# 2312_Ethernet.net
KiCad netlist of a schematic drawn in Altium Designer
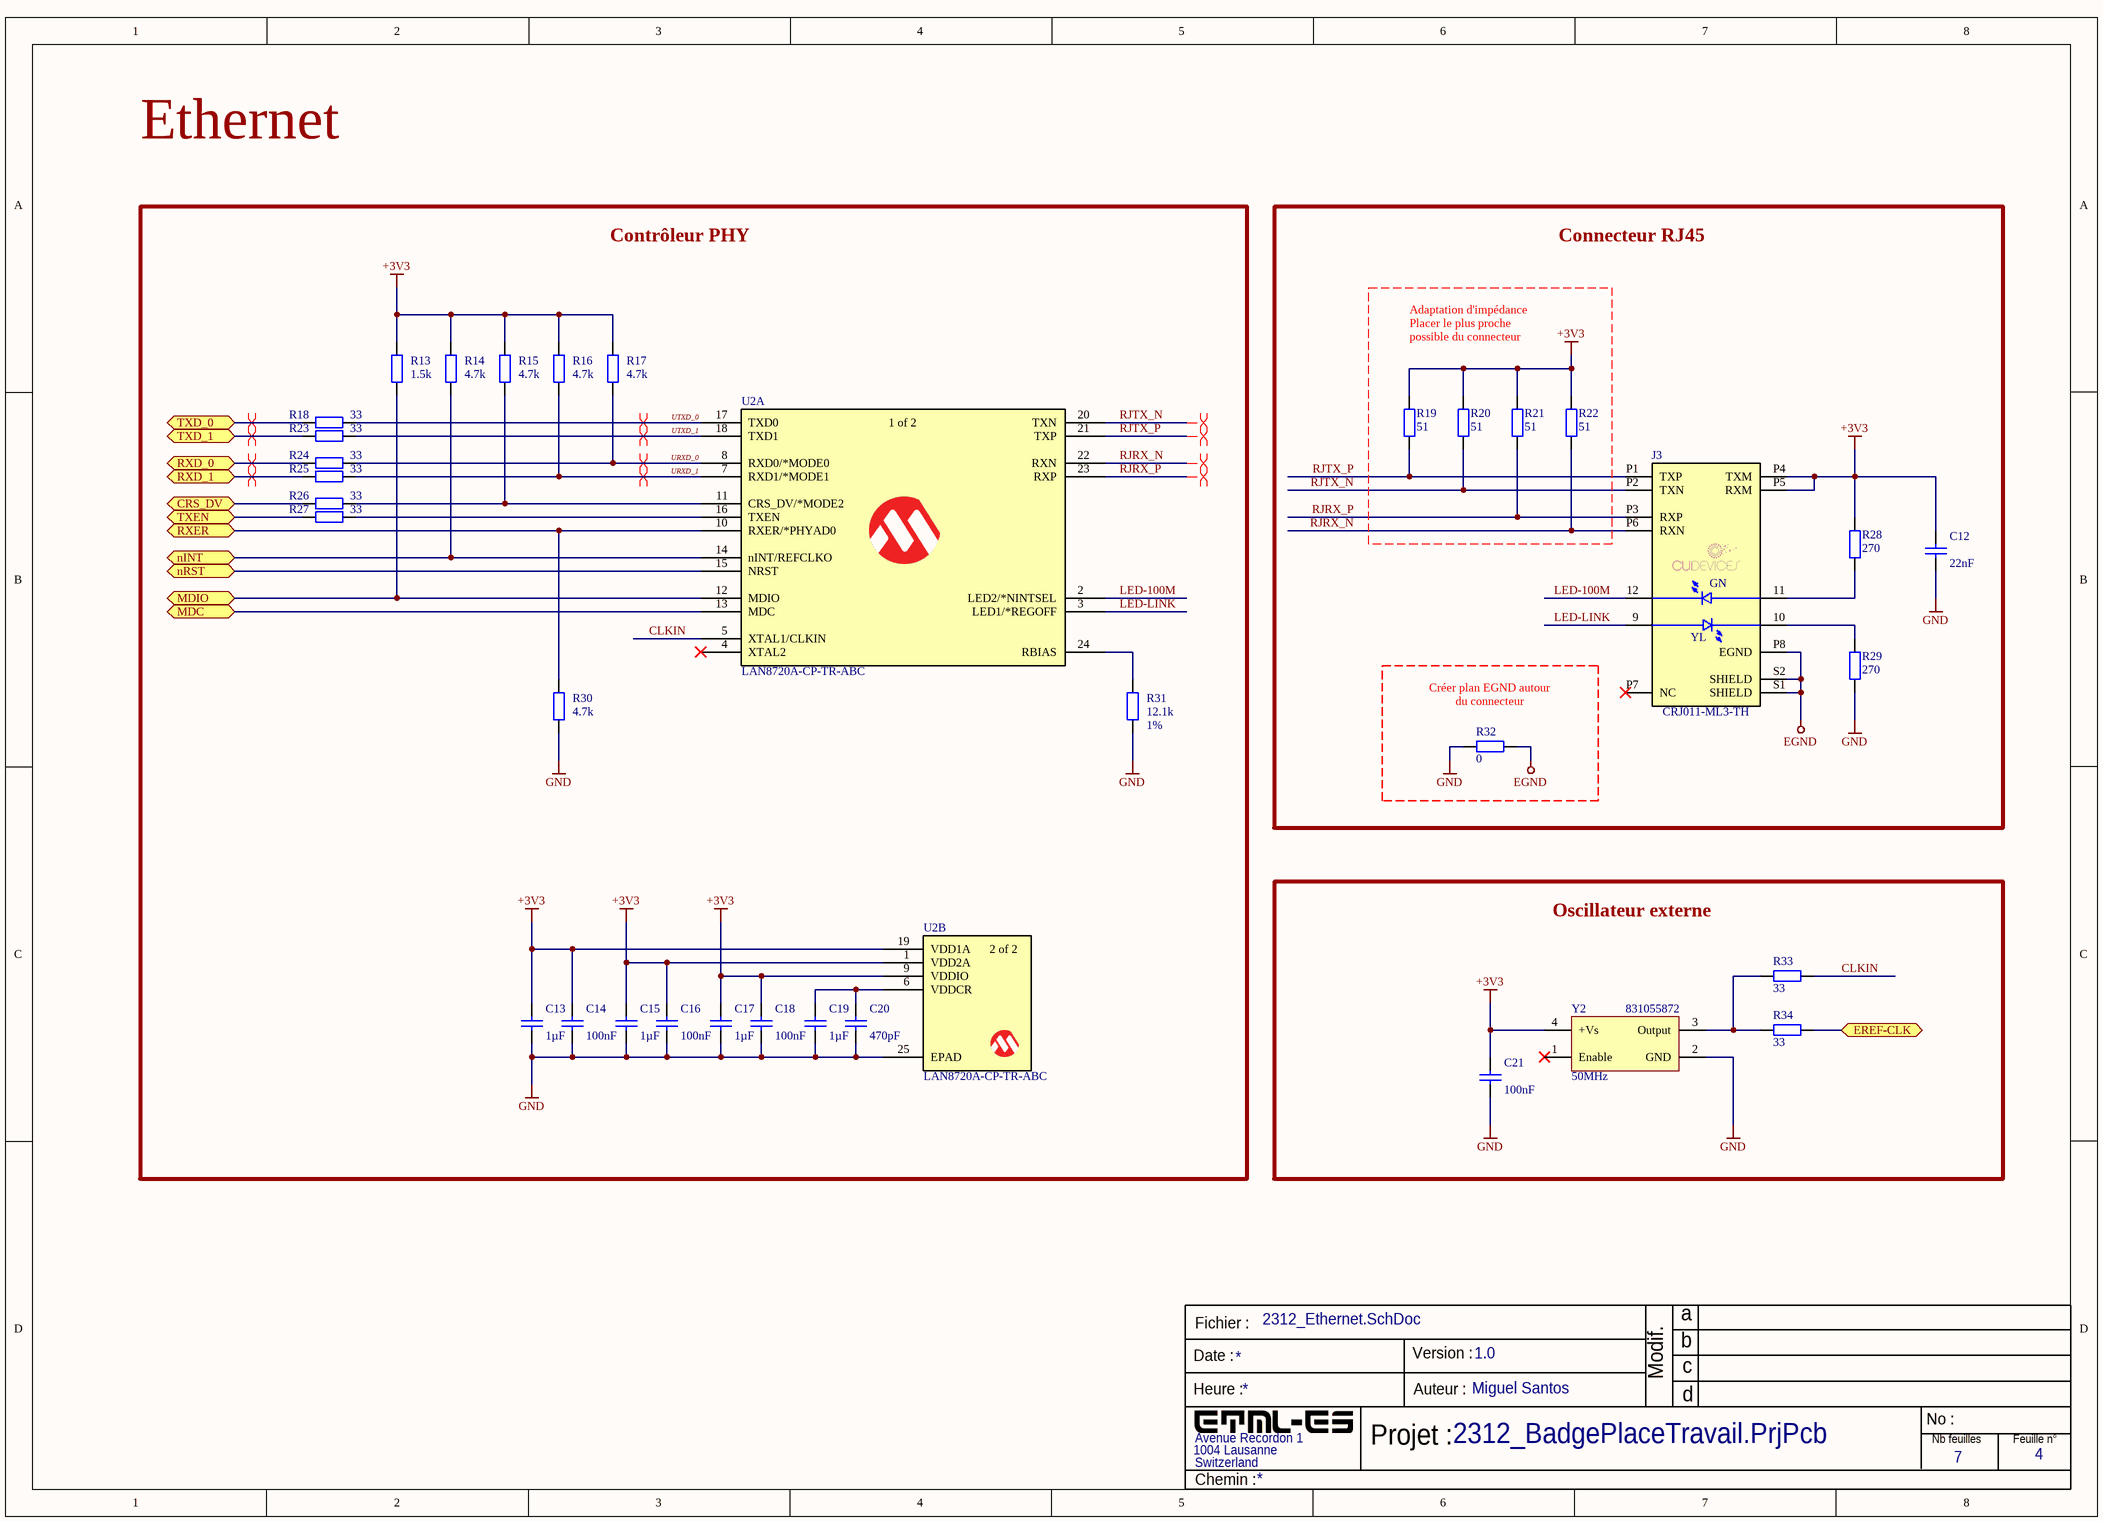
[diagram p0: 2312_Ethernet.SchDoc]

(export (version "E")
  (design (tool "Eeschema 10.0.6"))
  (components
    (comp (ref "C12")
      (value "885012207013")
      (footprint "WCAP-CSGP_0805_L2W1.25H0.8_Reflow")
      (description "WCAP-CSGP Multilayer Ceramic Chip Capacitor, General Purpose, size 0805, X7R, 22nF, 10VDC")
      (fields (field (name "MANUFACTURER") "Wurth Elektronik") (field (name "CAPACITANCE") "22nF"))
      (libsource (lib "WCAP-CSGP") (part "885012207013"))
    )
    (comp (ref "C13")
      (value "885012207022")
      (footprint "WCAP-CSGP_0805_L2W1.25H1.25")
      (description "WCAP-CSGP Multilayer Ceramic Chip Capacitor, General Purpose, size 0805, X7R, 1µF, 10VDC")
      (fields (field (name "MANUFACTURER") "Wurth Elektronik") (field (name "CAPACITANCE") "1µF"))
      (libsource (lib "WCAP-CSGP") (part "885012207022"))
    )
    (comp (ref "C14")
      (value "885012207016")
      (footprint "WCAP-CSGP_0805_L2W1.25H0.8_Reflow")
      (description "WCAP-CSGP Multilayer Ceramic Chip Capacitor, General Purpose, size 0805, X7R, 100nF, 10VDC")
      (fields (field (name "MANUFACTURER") "Wurth Elektronik") (field (name "CAPACITANCE") "100nF"))
      (libsource (lib "WCAP-CSGP") (part "885012207016"))
    )
    (comp (ref "C15")
      (value "885012207022")
      (footprint "WCAP-CSGP_0805_L2W1.25H1.25")
      (description "WCAP-CSGP Multilayer Ceramic Chip Capacitor, General Purpose, size 0805, X7R, 1µF, 10VDC")
      (fields (field (name "MANUFACTURER") "Wurth Elektronik") (field (name "CAPACITANCE") "1µF"))
      (libsource (lib "WCAP-CSGP") (part "885012207022"))
    )
    (comp (ref "C16")
      (value "885012207016")
      (footprint "WCAP-CSGP_0805_L2W1.25H0.8_Reflow")
      (description "WCAP-CSGP Multilayer Ceramic Chip Capacitor, General Purpose, size 0805, X7R, 100nF, 10VDC")
      (fields (field (name "MANUFACTURER") "Wurth Elektronik") (field (name "CAPACITANCE") "100nF"))
      (libsource (lib "WCAP-CSGP") (part "885012207016"))
    )
    (comp (ref "C17")
      (value "885012207022")
      (footprint "WCAP-CSGP_0805_L2W1.25H1.25")
      (description "WCAP-CSGP Multilayer Ceramic Chip Capacitor, General Purpose, size 0805, X7R, 1µF, 10VDC")
      (fields (field (name "MANUFACTURER") "Wurth Elektronik") (field (name "CAPACITANCE") "1µF"))
      (libsource (lib "WCAP-CSGP") (part "885012207022"))
    )
    (comp (ref "C18")
      (value "885012207016")
      (footprint "WCAP-CSGP_0805_L2W1.25H0.8_Reflow")
      (description "WCAP-CSGP Multilayer Ceramic Chip Capacitor, General Purpose, size 0805, X7R, 100nF, 10VDC")
      (fields (field (name "MANUFACTURER") "Wurth Elektronik") (field (name "CAPACITANCE") "100nF"))
      (libsource (lib "WCAP-CSGP") (part "885012207016"))
    )
    (comp (ref "C19")
      (value "885012207022")
      (footprint "WCAP-CSGP_0805_L2W1.25H1.25")
      (description "WCAP-CSGP Multilayer Ceramic Chip Capacitor, General Purpose, size 0805, X7R, 1µF, 10VDC")
      (fields (field (name "MANUFACTURER") "Wurth Elektronik") (field (name "CAPACITANCE") "1µF"))
      (libsource (lib "WCAP-CSGP") (part "885012207022"))
    )
    (comp (ref "C20")
      (value "885012007007")
      (footprint "WCAP-CSGP_0805_L2W1.25H0.8_Reflow")
      (description "WCAP-CSGP Multilayer Ceramic Chip Capacitor, General Purpose, size 0805, NP0, 470pF, 10VDC")
      (fields (field (name "MANUFACTURER") "Wurth Elektronik") (field (name "CAPACITANCE") "470pF"))
      (libsource (lib "WCAP-CSGP") (part "885012007007"))
    )
    (comp (ref "C21")
      (value "885012207016")
      (footprint "WCAP-CSGP_0805_L2W1.25H0.8_Reflow")
      (description "WCAP-CSGP Multilayer Ceramic Chip Capacitor, General Purpose, size 0805, X7R, 100nF, 10VDC")
      (fields (field (name "MANUFACTURER") "Wurth Elektronik") (field (name "CAPACITANCE") "100nF"))
      (libsource (lib "WCAP-CSGP") (part "885012207016"))
    )
    (comp (ref "J3")
      (value "CRJ011-ML3-TH")
      (footprint "CUI_CRJ011-ML3-TH")
      (description "Modular Jack")
      (libsource (lib "CUI_CRJ011-ML3-TH") (part "CRJ011-ML3-TH"))
    )
    (comp (ref "R13")
      (value "RES-0805")
      (footprint "2312-RES-0805")
      (description "SMD Resistor 0805, 1.5kΩ")
      (fields (field (name "RESISTANCE") "1.5k"))
      (libsource (lib "2312-MS-0805") (part "RES-0805"))
    )
    (comp (ref "R14")
      (value "RES-0805")
      (footprint "2312-RES-0805")
      (description "SMD Resistor 0805, 4.7kΩ")
      (fields (field (name "RESISTANCE") "4.7k"))
      (libsource (lib "2312-MS-0805") (part "RES-0805"))
    )
    (comp (ref "R15")
      (value "RES-0805")
      (footprint "2312-RES-0805")
      (description "SMD Resistor 0805, 4.7kΩ")
      (fields (field (name "RESISTANCE") "4.7k"))
      (libsource (lib "2312-MS-0805") (part "RES-0805"))
    )
    (comp (ref "R16")
      (value "RES-0805")
      (footprint "2312-RES-0805")
      (description "SMD Resistor 0805, 4.7kΩ")
      (fields (field (name "RESISTANCE") "4.7k"))
      (libsource (lib "2312-MS-0805") (part "RES-0805"))
    )
    (comp (ref "R17")
      (value "RES-0805")
      (footprint "2312-RES-0805")
      (description "SMD Resistor 0805, 4.7kΩ")
      (fields (field (name "RESISTANCE") "4.7k"))
      (libsource (lib "2312-MS-0805") (part "RES-0805"))
    )
    (comp (ref "R18")
      (value "RES-0805")
      (footprint "2312-RES-0805")
      (description "SMD Resistor 0805, 33Ω")
      (fields (field (name "RESISTANCE") "33"))
      (libsource (lib "2312-MS-0805") (part "RES-0805"))
    )
    (comp (ref "R19")
      (value "RES-0805")
      (footprint "2312-RES-0805")
      (description "SMD Resistor 0805, 51Ω")
      (fields (field (name "RESISTANCE") "51"))
      (libsource (lib "2312-MS-0805") (part "RES-0805"))
    )
    (comp (ref "R20")
      (value "RES-0805")
      (footprint "2312-RES-0805")
      (description "SMD Resistor 0805, 51Ω")
      (fields (field (name "RESISTANCE") "51"))
      (libsource (lib "2312-MS-0805") (part "RES-0805"))
    )
    (comp (ref "R21")
      (value "RES-0805")
      (footprint "2312-RES-0805")
      (description "SMD Resistor 0805, 51Ω")
      (fields (field (name "RESISTANCE") "51"))
      (libsource (lib "2312-MS-0805") (part "RES-0805"))
    )
    (comp (ref "R22")
      (value "RES-0805")
      (footprint "2312-RES-0805")
      (description "SMD Resistor 0805, 51Ω")
      (fields (field (name "RESISTANCE") "51"))
      (libsource (lib "2312-MS-0805") (part "RES-0805"))
    )
    (comp (ref "R23")
      (value "RES-0805")
      (footprint "2312-RES-0805")
      (description "SMD Resistor 0805, 33Ω")
      (fields (field (name "RESISTANCE") "33"))
      (libsource (lib "2312-MS-0805") (part "RES-0805"))
    )
    (comp (ref "R24")
      (value "RES-0805")
      (footprint "2312-RES-0805")
      (description "SMD Resistor 0805, 33Ω")
      (fields (field (name "RESISTANCE") "33"))
      (libsource (lib "2312-MS-0805") (part "RES-0805"))
    )
    (comp (ref "R25")
      (value "RES-0805")
      (footprint "2312-RES-0805")
      (description "SMD Resistor 0805, 33Ω")
      (fields (field (name "RESISTANCE") "33"))
      (libsource (lib "2312-MS-0805") (part "RES-0805"))
    )
    (comp (ref "R26")
      (value "RES-0805")
      (footprint "2312-RES-0805")
      (description "SMD Resistor 0805, 33Ω")
      (fields (field (name "RESISTANCE") "33"))
      (libsource (lib "2312-MS-0805") (part "RES-0805"))
    )
    (comp (ref "R27")
      (value "RES-0805")
      (footprint "2312-RES-0805")
      (description "SMD Resistor 0805, 33Ω")
      (fields (field (name "RESISTANCE") "33"))
      (libsource (lib "2312-MS-0805") (part "RES-0805"))
    )
    (comp (ref "R28")
      (value "RES-0805")
      (footprint "2312-RES-0805")
      (description "SMD Resistor 0805, 270Ω")
      (fields (field (name "RESISTANCE") "270"))
      (libsource (lib "2312-MS-0805") (part "RES-0805"))
    )
    (comp (ref "R29")
      (value "RES-0805")
      (footprint "2312-RES-0805")
      (description "SMD Resistor 0805, 270Ω")
      (fields (field (name "RESISTANCE") "270"))
      (libsource (lib "2312-MS-0805") (part "RES-0805"))
    )
    (comp (ref "R30")
      (value "RES-0805")
      (footprint "2312-RES-0805")
      (description "SMD Resistor 0805, 4.7kΩ")
      (fields (field (name "RESISTANCE") "4.7k"))
      (libsource (lib "2312-MS-0805") (part "RES-0805"))
    )
    (comp (ref "R31")
      (value "RES-0805")
      (footprint "2312-RES-0805")
      (description "SMD Resistor 0805, 12.1kΩ")
      (fields (field (name "RESISTANCE") "12.1k"))
      (libsource (lib "2312-MS-0805") (part "RES-0805"))
    )
    (comp (ref "R32")
      (value "RES-0805")
      (footprint "2312-RES-0805")
      (description "SMD Resistor 0805, 0Ω")
      (fields (field (name "RESISTANCE") "0"))
      (libsource (lib "2312-MS-0805") (part "RES-0805"))
    )
    (comp (ref "R33")
      (value "RES-0805")
      (footprint "2312-RES-0805")
      (description "SMD Resistor 0805, 33Ω")
      (fields (field (name "RESISTANCE") "33"))
      (libsource (lib "2312-MS-0805") (part "RES-0805"))
    )
    (comp (ref "R34")
      (value "RES-0805")
      (footprint "2312-RES-0805")
      (description "SMD Resistor 0805, 33Ω")
      (fields (field (name "RESISTANCE") "33"))
      (libsource (lib "2312-MS-0805") (part "RES-0805"))
    )
    (comp (ref "U2")
      (value "LAN8720A-CP-TR-ABC")
      (footprint "QFN24-6X6_MC_MCH")
      (description "No Description Available")
      (libsource (lib "LAN8720A-CP-TR-ABC") (part "LAN8720A-CP-TR-ABC"))
    )
    (comp (ref "Y2")
      (value "831055872")
      (footprint "WE-SPXO_CFPS-39")
      (description "WE-SPXO Simple Packaged Quartz Oscillator, SMT, CFPS-39, 50MHz, 3.3V")
      (fields (field (name "MANUFACTURER") "Wurth Elektronik") (field (name "FREQUENCY") "50MHz"))
      (libsource (lib "WE-SPXO") (part "831055872"))
    )
  )
  (nets
    (net (code "1") (name "+3V3") (class "Default")
      (node (ref "C12") (pin "2") (pinfunction "2_2") (pintype "passive"))
      (node (ref "C13") (pin "2") (pinfunction "2_2") (pintype "passive"))
      (node (ref "C14") (pin "2") (pinfunction "2_2") (pintype "passive"))
      (node (ref "C15") (pin "2") (pinfunction "2_2") (pintype "passive"))
      (node (ref "C16") (pin "2") (pinfunction "2_2") (pintype "passive"))
      (node (ref "C17") (pin "2") (pinfunction "2_2") (pintype "passive"))
      (node (ref "C18") (pin "2") (pinfunction "2_2") (pintype "passive"))
      (node (ref "C21") (pin "2") (pinfunction "2_2") (pintype "passive"))
      (node (ref "J3") (pin "P4") (pinfunction "TXM_P4") (pintype "passive"))
      (node (ref "J3") (pin "P5") (pinfunction "RXM_P5") (pintype "passive"))
      (node (ref "R13") (pin "2") (pinfunction "2_2") (pintype "passive"))
      (node (ref "R14") (pin "2") (pinfunction "2_2") (pintype "passive"))
      (node (ref "R15") (pin "2") (pinfunction "2_2") (pintype "passive"))
      (node (ref "R16") (pin "2") (pinfunction "2_2") (pintype "passive"))
      (node (ref "R17") (pin "2") (pinfunction "2_2") (pintype "passive"))
      (node (ref "R19") (pin "2") (pinfunction "2_2") (pintype "passive"))
      (node (ref "R20") (pin "2") (pinfunction "2_2") (pintype "passive"))
      (node (ref "R21") (pin "2") (pinfunction "2_2") (pintype "passive"))
      (node (ref "R22") (pin "2") (pinfunction "2_2") (pintype "passive"))
      (node (ref "R28") (pin "2") (pinfunction "2_2") (pintype "passive"))
      (node (ref "U2") (pin "1") (pinfunction "VDD2A_1") (pintype "power_in"))
      (node (ref "U2") (pin "19") (pinfunction "VDD1A_19") (pintype "power_in"))
      (node (ref "U2") (pin "9") (pinfunction "VDDIO_9") (pintype "power_in"))
      (node (ref "Y2") (pin "4") (pinfunction "+Vs_4") (pintype "passive"))
    )
    (net (code "2") (name "/CLKIN") (class "Default")
      (node (ref "R33") (pin "1") (pinfunction "1_1") (pintype "passive"))
      (node (ref "U2") (pin "5") (pinfunction "XTAL1/CLKIN_5") (pintype "passive"))
    )
    (net (code "3") (name "/CRS_DV") (class "Default")
      (node (ref "R26") (pin "2") (pinfunction "2_2") (pintype "passive"))
    )
    (net (code "4") (name "/EREF-CLK") (class "Default")
      (node (ref "R34") (pin "1") (pinfunction "1_1") (pintype "passive"))
    )
    (net (code "5") (name "/LED-100M") (class "Default")
      (node (ref "J3") (pin "12") (pinfunction "12_12") (pintype "passive"))
      (node (ref "U2") (pin "2") (pinfunction "LED2/*NINTSEL_2") (pintype "passive"))
    )
    (net (code "6") (name "/LED-LINK") (class "Default")
      (node (ref "J3") (pin "9") (pinfunction "9_9") (pintype "passive"))
      (node (ref "U2") (pin "3") (pinfunction "LED1/*REGOFF_3") (pintype "passive"))
    )
    (net (code "7") (name "/MDC") (class "Default")
      (node (ref "U2") (pin "13") (pinfunction "MDC_13") (pintype "passive"))
    )
    (net (code "8") (name "/MDIO") (class "Default")
      (node (ref "R13") (pin "1") (pinfunction "1_1") (pintype "passive"))
      (node (ref "U2") (pin "12") (pinfunction "MDIO_12") (pintype "passive"))
    )
    (net (code "9") (name "/RJRX_N") (class "Default")
      (node (ref "J3") (pin "P6") (pinfunction "RXN_P6") (pintype "passive"))
      (node (ref "R22") (pin "1") (pinfunction "1_1") (pintype "passive"))
      (node (ref "U2") (pin "22") (pinfunction "RXN_22") (pintype "passive"))
    )
    (net (code "10") (name "/RJRX_P") (class "Default")
      (node (ref "J3") (pin "P3") (pinfunction "RXP_P3") (pintype "passive"))
      (node (ref "R21") (pin "1") (pinfunction "1_1") (pintype "passive"))
      (node (ref "U2") (pin "23") (pinfunction "RXP_23") (pintype "passive"))
    )
    (net (code "11") (name "/RJTX_N") (class "Default")
      (node (ref "J3") (pin "P2") (pinfunction "TXN_P2") (pintype "passive"))
      (node (ref "R20") (pin "1") (pinfunction "1_1") (pintype "passive"))
      (node (ref "U2") (pin "20") (pinfunction "TXN_20") (pintype "passive"))
    )
    (net (code "12") (name "/RJTX_P") (class "Default")
      (node (ref "J3") (pin "P1") (pinfunction "TXP_P1") (pintype "passive"))
      (node (ref "R19") (pin "1") (pinfunction "1_1") (pintype "passive"))
      (node (ref "U2") (pin "21") (pinfunction "TXP_21") (pintype "passive"))
    )
    (net (code "13") (name "/RXD_0") (class "Default")
      (node (ref "R24") (pin "2") (pinfunction "2_2") (pintype "passive"))
    )
    (net (code "14") (name "/RXD_1") (class "Default")
      (node (ref "R25") (pin "2") (pinfunction "2_2") (pintype "passive"))
    )
    (net (code "15") (name "/RXER") (class "Default")
      (node (ref "R30") (pin "2") (pinfunction "2_2") (pintype "passive"))
      (node (ref "U2") (pin "10") (pinfunction "RXER/*PHYAD0_10") (pintype "passive"))
    )
    (net (code "16") (name "/TXD_0") (class "Default")
      (node (ref "R18") (pin "2") (pinfunction "2_2") (pintype "passive"))
    )
    (net (code "17") (name "/TXD_1") (class "Default")
      (node (ref "R23") (pin "2") (pinfunction "2_2") (pintype "passive"))
    )
    (net (code "18") (name "/TXEN") (class "Default")
      (node (ref "R27") (pin "2") (pinfunction "2_2") (pintype "passive"))
    )
    (net (code "19") (name "/URXD_0") (class "Default")
      (node (ref "R17") (pin "1") (pinfunction "1_1") (pintype "passive"))
      (node (ref "R24") (pin "1") (pinfunction "1_1") (pintype "passive"))
      (node (ref "U2") (pin "8") (pinfunction "RXD0/*MODE0_8") (pintype "passive"))
    )
    (net (code "20") (name "/URXD_1") (class "Default")
      (node (ref "R16") (pin "1") (pinfunction "1_1") (pintype "passive"))
      (node (ref "R25") (pin "1") (pinfunction "1_1") (pintype "passive"))
      (node (ref "U2") (pin "7") (pinfunction "RXD1/*MODE1_7") (pintype "passive"))
    )
    (net (code "21") (name "/UTXD_0") (class "Default")
      (node (ref "R18") (pin "1") (pinfunction "1_1") (pintype "passive"))
      (node (ref "U2") (pin "17") (pinfunction "TXD0_17") (pintype "passive"))
    )
    (net (code "22") (name "/UTXD_1") (class "Default")
      (node (ref "R23") (pin "1") (pinfunction "1_1") (pintype "passive"))
      (node (ref "U2") (pin "18") (pinfunction "TXD1_18") (pintype "passive"))
    )
    (net (code "23") (name "/nINT") (class "Default")
      (node (ref "R14") (pin "1") (pinfunction "1_1") (pintype "passive"))
      (node (ref "U2") (pin "14") (pinfunction "nINT/REFCLKO_14") (pintype "passive"))
    )
    (net (code "24") (name "/nRST") (class "Default")
      (node (ref "U2") (pin "15") (pinfunction "NRST_15") (pintype "passive"))
    )
    (net (code "25") (name "EGND") (class "Default")
      (node (ref "J3") (pin "P8") (pinfunction "EGND_P8") (pintype "passive"))
      (node (ref "J3") (pin "S1") (pinfunction "SHIELD_S1") (pintype "passive"))
      (node (ref "J3") (pin "S2") (pinfunction "SHIELD_S2") (pintype "passive"))
      (node (ref "R32") (pin "1") (pinfunction "1_1") (pintype "passive"))
    )
    (net (code "26") (name "GND") (class "Default")
      (node (ref "C12") (pin "1") (pinfunction "1_1") (pintype "passive"))
      (node (ref "C13") (pin "1") (pinfunction "1_1") (pintype "passive"))
      (node (ref "C14") (pin "1") (pinfunction "1_1") (pintype "passive"))
      (node (ref "C15") (pin "1") (pinfunction "1_1") (pintype "passive"))
      (node (ref "C16") (pin "1") (pinfunction "1_1") (pintype "passive"))
      (node (ref "C17") (pin "1") (pinfunction "1_1") (pintype "passive"))
      (node (ref "C18") (pin "1") (pinfunction "1_1") (pintype "passive"))
      (node (ref "C19") (pin "1") (pinfunction "1_1") (pintype "passive"))
      (node (ref "C20") (pin "1") (pinfunction "1_1") (pintype "passive"))
      (node (ref "C21") (pin "1") (pinfunction "1_1") (pintype "passive"))
      (node (ref "R29") (pin "1") (pinfunction "1_1") (pintype "passive"))
      (node (ref "R30") (pin "1") (pinfunction "1_1") (pintype "passive"))
      (node (ref "R31") (pin "1") (pinfunction "1_1") (pintype "passive"))
      (node (ref "R32") (pin "2") (pinfunction "2_2") (pintype "passive"))
      (node (ref "U2") (pin "25") (pinfunction "EPAD_25") (pintype "passive"))
      (node (ref "Y2") (pin "2") (pinfunction "GND_2") (pintype "passive"))
    )
    (net (code "27") (name "Net-(J3-Pad10)") (class "Default")
      (node (ref "J3") (pin "10") (pinfunction "10_10") (pintype "passive"))
      (node (ref "R29") (pin "2") (pinfunction "2_2") (pintype "passive"))
    )
    (net (code "28") (name "Net-(J3-Pad11)") (class "Default")
      (node (ref "J3") (pin "11") (pinfunction "11_11") (pintype "passive"))
      (node (ref "R28") (pin "1") (pinfunction "1_1") (pintype "passive"))
    )
    (net (code "29") (name "Net-(U2A-CRS_DV{slash}*MODE2)") (class "Default")
      (node (ref "R15") (pin "1") (pinfunction "1_1") (pintype "passive"))
      (node (ref "R26") (pin "1") (pinfunction "1_1") (pintype "passive"))
      (node (ref "U2") (pin "11") (pinfunction "CRS_DV/*MODE2_11") (pintype "passive"))
    )
    (net (code "30") (name "Net-(U2A-RBIAS)") (class "Default")
      (node (ref "R31") (pin "2") (pinfunction "2_2") (pintype "passive"))
      (node (ref "U2") (pin "24") (pinfunction "RBIAS_24") (pintype "passive"))
    )
    (net (code "31") (name "Net-(U2A-TXEN)") (class "Default")
      (node (ref "R27") (pin "1") (pinfunction "1_1") (pintype "passive"))
      (node (ref "U2") (pin "16") (pinfunction "TXEN_16") (pintype "passive"))
    )
    (net (code "32") (name "Net-(U2B-VDDCR)") (class "Default")
      (node (ref "C19") (pin "2") (pinfunction "2_2") (pintype "passive"))
      (node (ref "C20") (pin "2") (pinfunction "2_2") (pintype "passive"))
      (node (ref "U2") (pin "6") (pinfunction "VDDCR_6") (pintype "power_in"))
    )
    (net (code "33") (name "Net-(Y2-Output)") (class "Default")
      (node (ref "R33") (pin "2") (pinfunction "2_2") (pintype "passive"))
      (node (ref "R34") (pin "2") (pinfunction "2_2") (pintype "passive"))
      (node (ref "Y2") (pin "3") (pinfunction "Output_3") (pintype "passive"))
    )
    (net (code "34") (name "unconnected-(J3-NC-PadP7)") (class "Default")
      (node (ref "J3") (pin "P7") (pinfunction "NC_P7") (pintype "passive+no_connect"))
    )
    (net (code "35") (name "unconnected-(U2A-XTAL2-Pad4)") (class "Default")
      (node (ref "U2") (pin "4") (pinfunction "XTAL2_4") (pintype "passive+no_connect"))
    )
    (net (code "36") (name "unconnected-(Y2-Enable-Pad1)") (class "Default")
      (node (ref "Y2") (pin "1") (pinfunction "Enable_1") (pintype "passive+no_connect"))
    )
  )
)
